# Filter_Low_Pass.net
KiCad netlist of a schematic drawn in Altium Designer
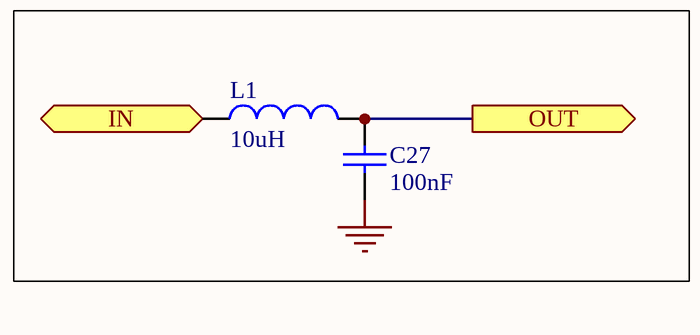
[diagram p0: Filter_Low Pass.SchDoc]

(export (version "E")
  (design (tool "Eeschema 10.0.6"))
  (components
    (comp (ref "C27")
      (value "100nF")
      (footprint "0805")
      (description "Capacitor")
      (fields (field (name "MANUFACTURER") "Generic Components") (field (name "PUBLISHER") "Altium Limited"))
      (libsource (lib "Miscellaneous Devices") (part "Cap"))
    )
    (comp (ref "L1")
      (value "10uH")
      (footprint "0805")
      (description "Inductor")
      (libsource (lib "my Libraries") (part "Inductor"))
    )
  )
  (nets
    (net (code "1") (name "/IN") (class "Default")
      (node (ref "L1") (pin "1") (pinfunction "1_1") (pintype "passive"))
    )
    (net (code "2") (name "/OUT") (class "Default")
      (node (ref "C27") (pin "2") (pinfunction "2_2") (pintype "passive"))
      (node (ref "L1") (pin "2") (pinfunction "2_2") (pintype "passive"))
    )
    (net (code "3") (name "GND") (class "Default")
      (node (ref "C27") (pin "1") (pinfunction "1_1") (pintype "passive"))
    )
  )
)
